# ProgTool.net
KiCad netlist of a schematic drawn in Altium Designer
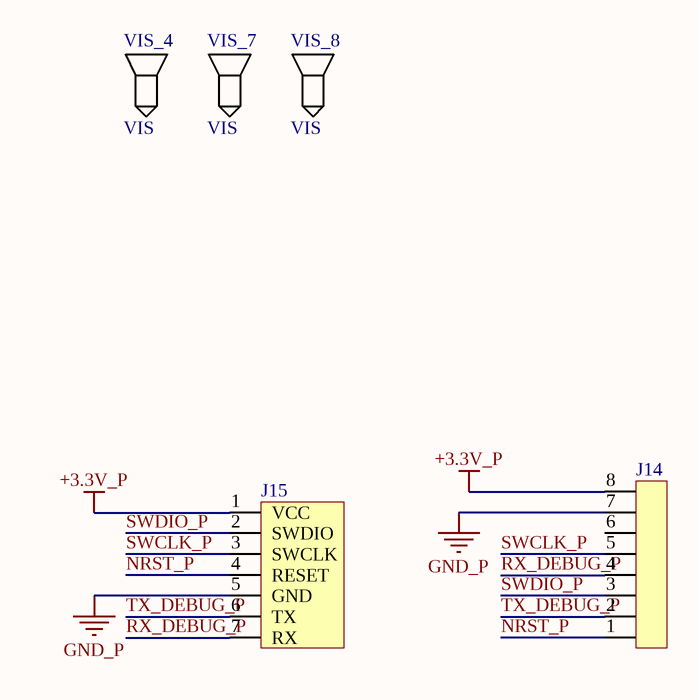
[diagram p0: ProgTool.SchDoc]

(export (version "E")
  (design (tool "Eeschema 10.0.6"))
  (components
    (comp (ref "J14")
      (value "~")
      (footprint "BARF-2X4")
      (description "Connector 8 points")
      (libsource (lib "MyLibrary") (part "CON-8"))
    )
    (comp (ref "J15")
      (value "~")
      (footprint "CON_PROG")
      (description "Programming Connector")
      (libsource (lib "MyLibrary") (part "CON-PROG"))
    )
    (comp (ref "VIS_4") (value "VIS") (footprint "HOLE3.5mm") (libsource (lib "PROTEL") (part "VIS")))
    (comp (ref "VIS_7") (value "VIS") (footprint "HOLE3.5mm") (libsource (lib "PROTEL") (part "VIS")))
    (comp (ref "VIS_8") (value "VIS") (footprint "HOLE3.5mm") (libsource (lib "PROTEL") (part "VIS")))
  )
  (nets
    (net (code "1") (name "+3.3V_P") (class "Default")
      (node (ref "J14") (pin "8") (pinfunction "8_8") (pintype "passive"))
      (node (ref "J15") (pin "1") (pinfunction "VCC_1") (pintype "passive"))
    )
    (net (code "2") (name "/NRST_P") (class "Default")
      (node (ref "J14") (pin "1") (pinfunction "1_1") (pintype "passive"))
      (node (ref "J15") (pin "4") (pinfunction "RESET_4") (pintype "passive"))
    )
    (net (code "3") (name "/RX_DEBUG_P") (class "Default")
      (node (ref "J14") (pin "4") (pinfunction "4_4") (pintype "passive"))
      (node (ref "J15") (pin "7") (pinfunction "RX_7") (pintype "passive"))
    )
    (net (code "4") (name "/SWCLK_P") (class "Default")
      (node (ref "J14") (pin "5") (pinfunction "5_5") (pintype "passive"))
      (node (ref "J15") (pin "3") (pinfunction "SWCLK_3") (pintype "passive"))
    )
    (net (code "5") (name "/SWDIO_P") (class "Default")
      (node (ref "J14") (pin "3") (pinfunction "3_3") (pintype "passive"))
      (node (ref "J15") (pin "2") (pinfunction "SWDIO_2") (pintype "passive"))
    )
    (net (code "6") (name "/TX_DEBUG_P") (class "Default")
      (node (ref "J14") (pin "2") (pinfunction "2_2") (pintype "passive"))
      (node (ref "J15") (pin "6") (pinfunction "TX_6") (pintype "passive"))
    )
    (net (code "7") (name "GND_P") (class "Default")
      (node (ref "J14") (pin "7") (pinfunction "7_7") (pintype "passive"))
      (node (ref "J15") (pin "5") (pinfunction "GND_5") (pintype "passive"))
    )
    (net (code "8") (name "unconnected-(J14-Pad6)") (class "Default")
      (node (ref "J14") (pin "6") (pinfunction "6_6") (pintype "passive"))
    )
  )
)
